# bmsMaster_main.net
KiCad netlist of a schematic drawn in Altium Designer
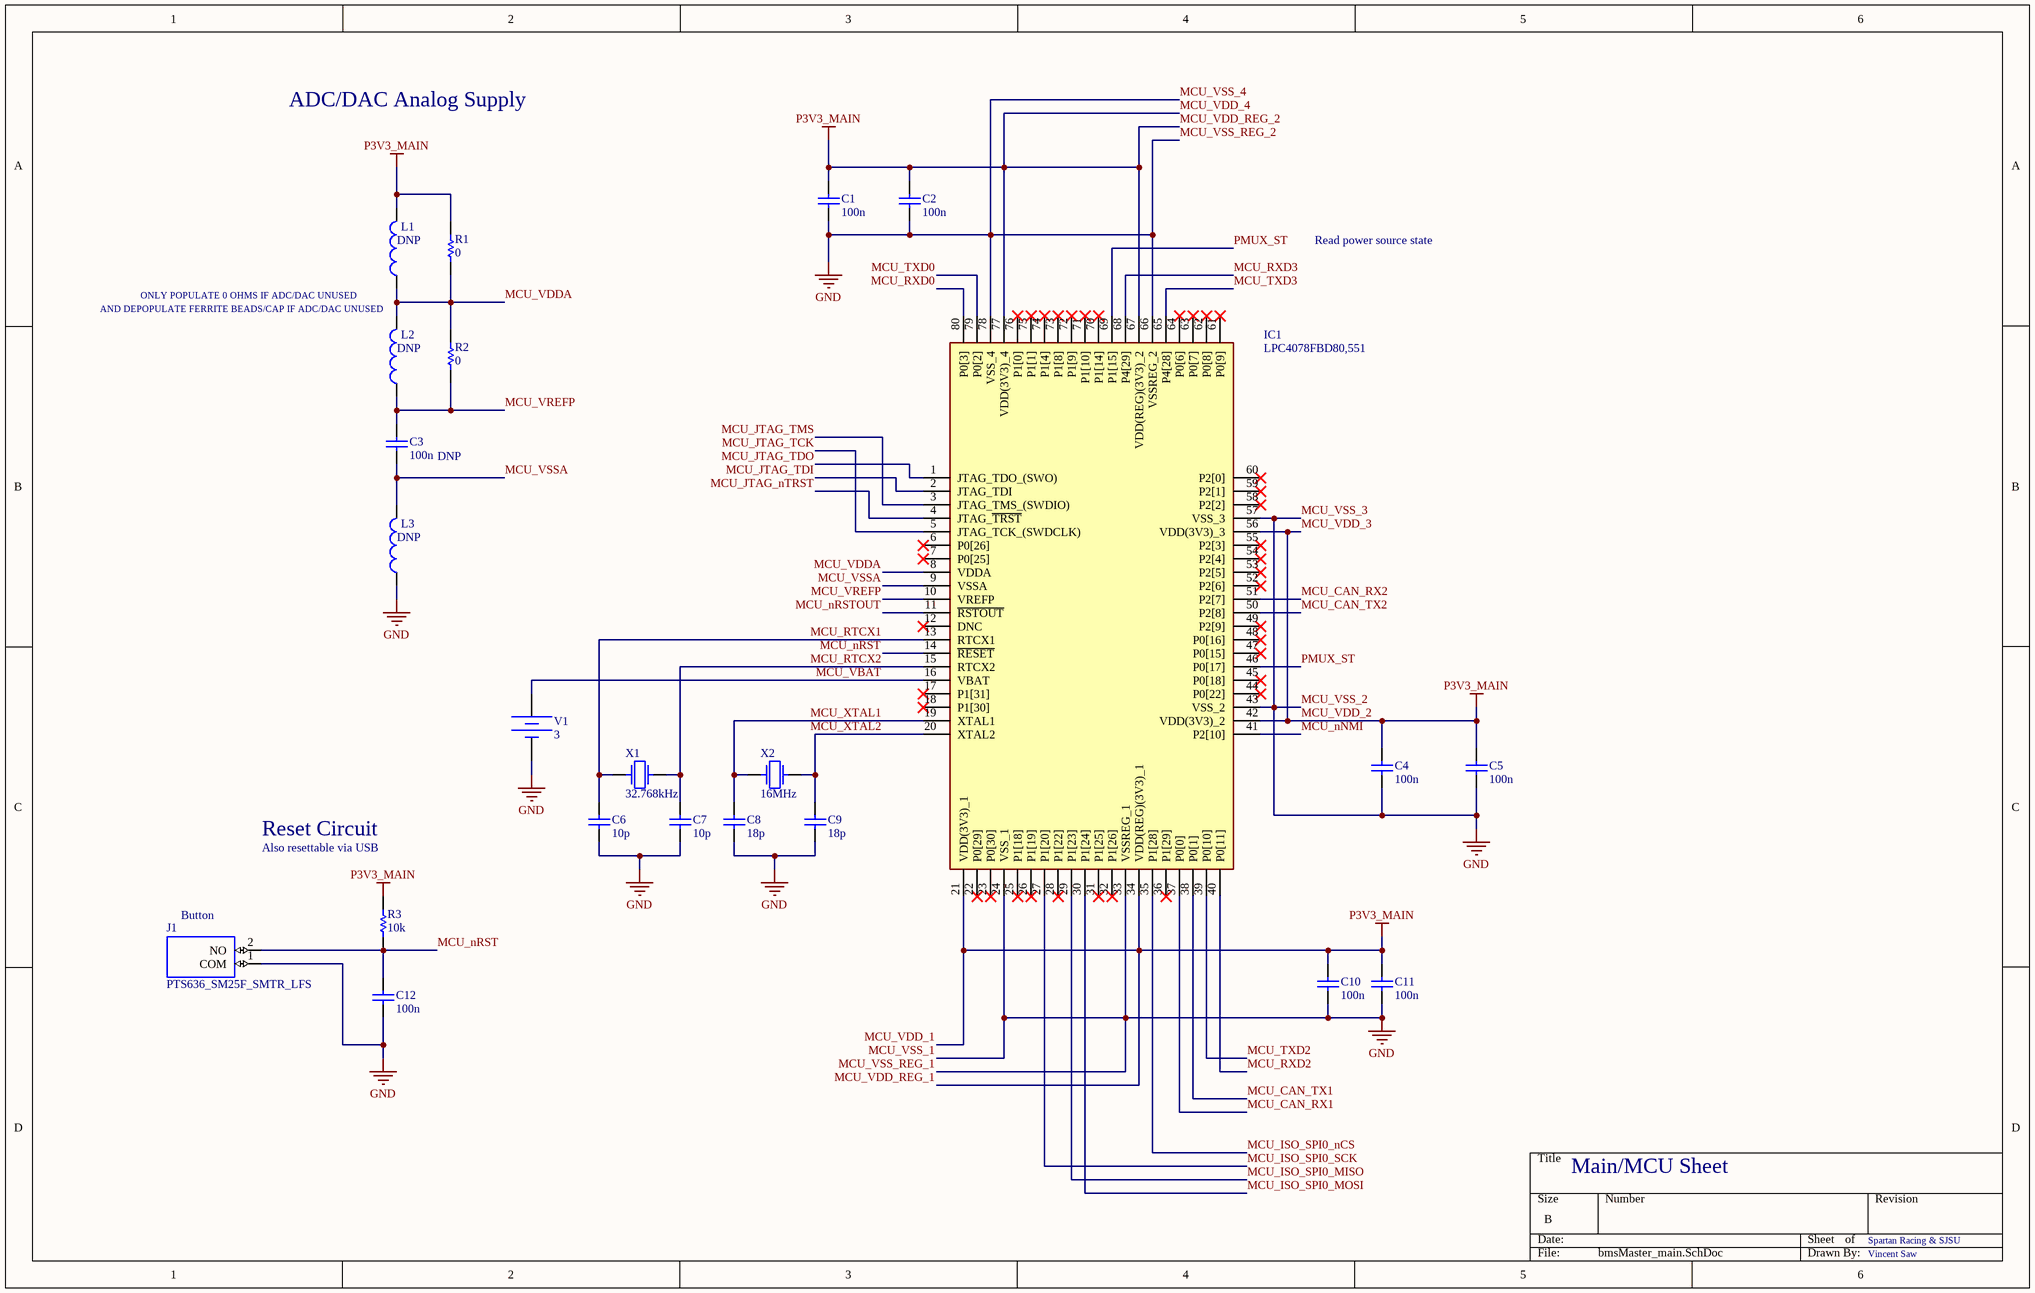
[diagram p0: bmsMaster_main.SchDoc]

(export (version "E")
  (design (tool "Eeschema 10.0.6"))
  (components
    (comp (ref "C1")
      (value "100n")
      (description "Capacitor")
      (libsource (lib "Simulation Generic Components") (part "Capacitor"))
    )
    (comp (ref "C2")
      (value "100n")
      (description "Capacitor")
      (libsource (lib "Simulation Generic Components") (part "Capacitor"))
    )
    (comp (ref "C3")
      (value "100n")
      (description "Capacitor")
      (libsource (lib "Simulation Generic Components") (part "Capacitor"))
    )
    (comp (ref "C4")
      (value "100n")
      (description "Capacitor")
      (libsource (lib "Simulation Generic Components") (part "Capacitor"))
    )
    (comp (ref "C5")
      (value "100n")
      (description "Capacitor")
      (libsource (lib "Simulation Generic Components") (part "Capacitor"))
    )
    (comp (ref "C6")
      (value "10p")
      (description "Capacitor")
      (libsource (lib "Simulation Generic Components") (part "Capacitor"))
    )
    (comp (ref "C7")
      (value "10p")
      (description "Capacitor")
      (libsource (lib "Simulation Generic Components") (part "Capacitor"))
    )
    (comp (ref "C8")
      (value "18p")
      (description "Capacitor")
      (libsource (lib "Simulation Generic Components") (part "Capacitor"))
    )
    (comp (ref "C9")
      (value "18p")
      (description "Capacitor")
      (libsource (lib "Simulation Generic Components") (part "Capacitor"))
    )
    (comp (ref "C10")
      (value "100n")
      (description "Capacitor")
      (libsource (lib "Simulation Generic Components") (part "Capacitor"))
    )
    (comp (ref "C11")
      (value "100n")
      (description "Capacitor")
      (libsource (lib "Simulation Generic Components") (part "Capacitor"))
    )
    (comp (ref "C12")
      (value "100n")
      (description "Capacitor")
      (libsource (lib "Simulation Generic Components") (part "Capacitor"))
    )
    (comp (ref "IC1")
      (value "LPC4078FBD80,551")
      (footprint "SamacSys:QFP50P1400X1400X160-80N")
      (description "Integrated Circuit")
      (fields (field (name "MOUSER PART NUMBER") "771-LPC4078FBD80551"))
      (libsource (lib "*") (part "LPC4078FBD80,551"))
    )
    (comp (ref "J1")
      (value "PTS636_SM25F_SMTR_LFS")
      (footprint "PTS636SM25FSMTRLFS")
      (description "Tactile Switch SPST-NO Top Actuated Surface Mount")
      (fields (field (name "MF") "C&K") (field (name "MP") "PTS636 SM25F SMTR LFS"))
      (libsource (lib "PTS636_SM25F_SMTR_LFS") (part "PTS636_SM25F_SMTR_LFS"))
    )
    (comp (ref "L1") (value "Inductor") (libsource (lib "Simulation Generic Components") (part "Inductor")))
    (comp (ref "L2") (value "Inductor") (libsource (lib "Simulation Generic Components") (part "Inductor")))
    (comp (ref "L3") (value "Inductor") (libsource (lib "Simulation Generic Components") (part "Inductor")))
    (comp (ref "R1")
      (value "0")
      (description "Resistor")
      (libsource (lib "Simulation Generic Components") (part "Resistor"))
    )
    (comp (ref "R2")
      (value "0")
      (description "Resistor")
      (libsource (lib "Simulation Generic Components") (part "Resistor"))
    )
    (comp (ref "R3")
      (value "10k")
      (description "Resistor")
      (libsource (lib "Simulation Generic Components") (part "Resistor"))
    )
    (comp (ref "V1")
      (value "Constant Voltage Source")
      (fields (field (name "DC MAGNITUDE") "3"))
      (libsource (lib "Simulation Generic Components") (part "Battery"))
    )
    (comp (ref "X1")
      (value "Crystal")
      (fields (field (name "F0") "32.768kHz"))
      (libsource (lib "Simulation Generic Components") (part "Crystal"))
    )
    (comp (ref "X2")
      (value "Crystal")
      (fields (field (name "F0") "16MHz"))
      (libsource (lib "Simulation Generic Components") (part "Crystal"))
    )
  )
  (nets
    (net (code "1") (name "/MCU_CAN_RX1") (class "Default")
      (node (ref "IC1") (pin "37") (pinfunction "P0[0]_37") (pintype "passive"))
    )
    (net (code "2") (name "/MCU_CAN_RX2") (class "Default")
      (node (ref "IC1") (pin "51") (pinfunction "P2[7]_51") (pintype "passive"))
    )
    (net (code "3") (name "/MCU_CAN_TX1") (class "Default")
      (node (ref "IC1") (pin "38") (pinfunction "P0[1]_38") (pintype "passive"))
    )
    (net (code "4") (name "/MCU_CAN_TX2") (class "Default")
      (node (ref "IC1") (pin "50") (pinfunction "P2[8]_50") (pintype "passive"))
    )
    (net (code "5") (name "/MCU_ISO_SPI0_MISO") (class "Default")
      (node (ref "IC1") (pin "29") (pinfunction "P1[23]_29") (pintype "passive"))
    )
    (net (code "6") (name "/MCU_ISO_SPI0_MOSI") (class "Default")
      (node (ref "IC1") (pin "30") (pinfunction "P1[24]_30") (pintype "passive"))
    )
    (net (code "7") (name "/MCU_ISO_SPI0_SCK") (class "Default")
      (node (ref "IC1") (pin "27") (pinfunction "P1[20]_27") (pintype "passive"))
    )
    (net (code "8") (name "/MCU_ISO_SPI0_nCS") (class "Default")
      (node (ref "IC1") (pin "35") (pinfunction "P1[28]_35") (pintype "passive"))
    )
    (net (code "9") (name "/MCU_JTAG_TCK") (class "Default")
      (node (ref "IC1") (pin "5") (pinfunction "JTAG_TCK_(SWDCLK)_5") (pintype "passive"))
    )
    (net (code "10") (name "/MCU_JTAG_TDI") (class "Default")
      (node (ref "IC1") (pin "2") (pinfunction "JTAG_TDI_2") (pintype "passive"))
    )
    (net (code "11") (name "/MCU_JTAG_TDO") (class "Default")
      (node (ref "IC1") (pin "1") (pinfunction "JTAG_TDO_(SWO)_1") (pintype "passive"))
    )
    (net (code "12") (name "/MCU_JTAG_TMS") (class "Default")
      (node (ref "IC1") (pin "3") (pinfunction "JTAG_TMS_(SWDIO)_3") (pintype "passive"))
    )
    (net (code "13") (name "/MCU_JTAG_nTRST") (class "Default")
      (node (ref "IC1") (pin "4") (pinfunction "JTAG_~{TRST}_4") (pintype "passive"))
    )
    (net (code "14") (name "/MCU_RTCX1") (class "Default")
      (node (ref "C6") (pin "2") (pinfunction "2_2") (pintype "passive"))
      (node (ref "IC1") (pin "13") (pinfunction "RTCX1_13") (pintype "passive"))
      (node (ref "X1") (pin "1") (pinfunction "1_1") (pintype "passive"))
    )
    (net (code "15") (name "/MCU_RTCX2") (class "Default")
      (node (ref "C7") (pin "2") (pinfunction "2_2") (pintype "passive"))
      (node (ref "IC1") (pin "15") (pinfunction "RTCX2_15") (pintype "passive"))
      (node (ref "X1") (pin "2") (pinfunction "2_2") (pintype "passive"))
    )
    (net (code "16") (name "/MCU_RXD0") (class "Default")
      (node (ref "IC1") (pin "80") (pinfunction "P0[3]_80") (pintype "passive"))
    )
    (net (code "17") (name "/MCU_RXD2") (class "Default")
      (node (ref "IC1") (pin "40") (pinfunction "P0[11]_40") (pintype "passive"))
    )
    (net (code "18") (name "/MCU_RXD3") (class "Default")
      (node (ref "IC1") (pin "68") (pinfunction "P4[29]_68") (pintype "passive"))
    )
    (net (code "19") (name "/MCU_TXD0") (class "Default")
      (node (ref "IC1") (pin "79") (pinfunction "P0[2]_79") (pintype "passive"))
    )
    (net (code "20") (name "/MCU_TXD2") (class "Default")
      (node (ref "IC1") (pin "39") (pinfunction "P0[10]_39") (pintype "passive"))
    )
    (net (code "21") (name "/MCU_TXD3") (class "Default")
      (node (ref "IC1") (pin "65") (pinfunction "P4[28]_65") (pintype "passive"))
    )
    (net (code "22") (name "/MCU_VBAT") (class "Default")
      (node (ref "IC1") (pin "16") (pinfunction "VBAT_16") (pintype "passive"))
      (node (ref "V1") (pin "1") (pinfunction "1_1") (pintype "passive"))
    )
    (net (code "23") (name "/MCU_VDDA") (class "Default")
      (node (ref "IC1") (pin "8") (pinfunction "VDDA_8") (pintype "passive"))
      (node (ref "L1") (pin "1") (pinfunction "1_1") (pintype "passive"))
      (node (ref "L2") (pin "2") (pinfunction "2_2") (pintype "passive"))
      (node (ref "R1") (pin "1") (pinfunction "1_1") (pintype "passive"))
      (node (ref "R2") (pin "2") (pinfunction "2_2") (pintype "passive"))
    )
    (net (code "24") (name "/MCU_VREFP") (class "Default")
      (node (ref "C3") (pin "2") (pinfunction "2_2") (pintype "passive"))
      (node (ref "IC1") (pin "10") (pinfunction "VREFP_10") (pintype "passive"))
      (node (ref "L2") (pin "1") (pinfunction "1_1") (pintype "passive"))
      (node (ref "R2") (pin "1") (pinfunction "1_1") (pintype "passive"))
    )
    (net (code "25") (name "/MCU_VSSA") (class "Default")
      (node (ref "C3") (pin "1") (pinfunction "1_1") (pintype "passive"))
      (node (ref "IC1") (pin "9") (pinfunction "VSSA_9") (pintype "passive"))
      (node (ref "L3") (pin "2") (pinfunction "2_2") (pintype "passive"))
    )
    (net (code "26") (name "/MCU_XTAL1") (class "Default")
      (node (ref "C8") (pin "2") (pinfunction "2_2") (pintype "passive"))
      (node (ref "IC1") (pin "19") (pinfunction "XTAL1_19") (pintype "passive"))
      (node (ref "X2") (pin "1") (pinfunction "1_1") (pintype "passive"))
    )
    (net (code "27") (name "/MCU_XTAL2") (class "Default")
      (node (ref "C9") (pin "2") (pinfunction "2_2") (pintype "passive"))
      (node (ref "IC1") (pin "20") (pinfunction "XTAL2_20") (pintype "passive"))
      (node (ref "X2") (pin "2") (pinfunction "2_2") (pintype "passive"))
    )
    (net (code "28") (name "/MCU_nNMI") (class "Default")
      (node (ref "IC1") (pin "41") (pinfunction "P2[10]_41") (pintype "passive"))
    )
    (net (code "29") (name "/MCU_nRST") (class "Default")
      (node (ref "C12") (pin "2") (pinfunction "2_2") (pintype "passive"))
      (node (ref "IC1") (pin "14") (pinfunction "~{RESET}_14") (pintype "passive"))
      (node (ref "J1") (pin "2") (pinfunction "NO_2") (pintype "bidirectional"))
      (node (ref "R3") (pin "1") (pinfunction "1_1") (pintype "passive"))
    )
    (net (code "30") (name "/MCU_nRSTOUT") (class "Default")
      (node (ref "IC1") (pin "11") (pinfunction "~{RSTOUT}_11") (pintype "passive"))
    )
    (net (code "31") (name "/PMUX_ST") (class "Default")
      (node (ref "IC1") (pin "46") (pinfunction "P0[17]_46") (pintype "passive"))
      (node (ref "IC1") (pin "69") (pinfunction "P1[15]_69") (pintype "passive"))
    )
    (net (code "32") (name "GND") (class "Default")
      (node (ref "C1") (pin "1") (pinfunction "1_1") (pintype "passive"))
      (node (ref "C10") (pin "1") (pinfunction "1_1") (pintype "passive"))
      (node (ref "C11") (pin "1") (pinfunction "1_1") (pintype "passive"))
      (node (ref "C12") (pin "1") (pinfunction "1_1") (pintype "passive"))
      (node (ref "C2") (pin "1") (pinfunction "1_1") (pintype "passive"))
      (node (ref "C4") (pin "1") (pinfunction "1_1") (pintype "passive"))
      (node (ref "C5") (pin "1") (pinfunction "1_1") (pintype "passive"))
      (node (ref "C6") (pin "1") (pinfunction "1_1") (pintype "passive"))
      (node (ref "C7") (pin "1") (pinfunction "1_1") (pintype "passive"))
      (node (ref "C8") (pin "1") (pinfunction "1_1") (pintype "passive"))
      (node (ref "C9") (pin "1") (pinfunction "1_1") (pintype "passive"))
      (node (ref "IC1") (pin "24") (pinfunction "VSS_1_24") (pintype "passive"))
      (node (ref "IC1") (pin "33") (pinfunction "VSSREG_1_33") (pintype "passive"))
      (node (ref "IC1") (pin "43") (pinfunction "VSS_2_43") (pintype "passive"))
      (node (ref "IC1") (pin "57") (pinfunction "VSS_3_57") (pintype "passive"))
      (node (ref "IC1") (pin "66") (pinfunction "VSSREG_2_66") (pintype "passive"))
      (node (ref "IC1") (pin "78") (pinfunction "VSS_4_78") (pintype "passive"))
      (node (ref "J1") (pin "1") (pinfunction "COM_1") (pintype "bidirectional"))
      (node (ref "L3") (pin "1") (pinfunction "1_1") (pintype "passive"))
      (node (ref "V1") (pin "2") (pinfunction "2_2") (pintype "passive"))
    )
    (net (code "33") (name "P3V3_MAIN") (class "Default")
      (node (ref "C1") (pin "2") (pinfunction "2_2") (pintype "passive"))
      (node (ref "C10") (pin "2") (pinfunction "2_2") (pintype "passive"))
      (node (ref "C11") (pin "2") (pinfunction "2_2") (pintype "passive"))
      (node (ref "C2") (pin "2") (pinfunction "2_2") (pintype "passive"))
      (node (ref "C4") (pin "2") (pinfunction "2_2") (pintype "passive"))
      (node (ref "C5") (pin "2") (pinfunction "2_2") (pintype "passive"))
      (node (ref "IC1") (pin "21") (pinfunction "VDD(3V3)_1_21") (pintype "passive"))
      (node (ref "IC1") (pin "34") (pinfunction "VDD(REG)(3V3)_1_34") (pintype "passive"))
      (node (ref "IC1") (pin "42") (pinfunction "VDD(3V3)_2_42") (pintype "passive"))
      (node (ref "IC1") (pin "56") (pinfunction "VDD(3V3)_3_56") (pintype "passive"))
      (node (ref "IC1") (pin "67") (pinfunction "VDD(REG)(3V3)_2_67") (pintype "passive"))
      (node (ref "IC1") (pin "77") (pinfunction "VDD(3V3)_4_77") (pintype "passive"))
      (node (ref "L1") (pin "2") (pinfunction "2_2") (pintype "passive"))
      (node (ref "R1") (pin "2") (pinfunction "2_2") (pintype "passive"))
      (node (ref "R3") (pin "2") (pinfunction "2_2") (pintype "passive"))
    )
    (net (code "34") (name "unconnected-(IC1-DNC-Pad12)") (class "Default")
      (node (ref "IC1") (pin "12") (pinfunction "DNC_12") (pintype "passive+no_connect"))
    )
    (net (code "35") (name "unconnected-(IC1-P0[6]-Pad64)") (class "Default")
      (node (ref "IC1") (pin "64") (pinfunction "P0[6]_64") (pintype "passive+no_connect"))
    )
    (net (code "36") (name "unconnected-(IC1-P0[7]-Pad63)") (class "Default")
      (node (ref "IC1") (pin "63") (pinfunction "P0[7]_63") (pintype "passive+no_connect"))
    )
    (net (code "37") (name "unconnected-(IC1-P0[8]-Pad62)") (class "Default")
      (node (ref "IC1") (pin "62") (pinfunction "P0[8]_62") (pintype "passive+no_connect"))
    )
    (net (code "38") (name "unconnected-(IC1-P0[9]-Pad61)") (class "Default")
      (node (ref "IC1") (pin "61") (pinfunction "P0[9]_61") (pintype "passive+no_connect"))
    )
    (net (code "39") (name "unconnected-(IC1-P0[15]-Pad47)") (class "Default")
      (node (ref "IC1") (pin "47") (pinfunction "P0[15]_47") (pintype "passive+no_connect"))
    )
    (net (code "40") (name "unconnected-(IC1-P0[16]-Pad48)") (class "Default")
      (node (ref "IC1") (pin "48") (pinfunction "P0[16]_48") (pintype "passive+no_connect"))
    )
    (net (code "41") (name "unconnected-(IC1-P0[18]-Pad45)") (class "Default")
      (node (ref "IC1") (pin "45") (pinfunction "P0[18]_45") (pintype "passive+no_connect"))
    )
    (net (code "42") (name "unconnected-(IC1-P0[22]-Pad44)") (class "Default")
      (node (ref "IC1") (pin "44") (pinfunction "P0[22]_44") (pintype "passive+no_connect"))
    )
    (net (code "43") (name "unconnected-(IC1-P0[25]-Pad7)") (class "Default")
      (node (ref "IC1") (pin "7") (pinfunction "P0[25]_7") (pintype "passive+no_connect"))
    )
    (net (code "44") (name "unconnected-(IC1-P0[26]-Pad6)") (class "Default")
      (node (ref "IC1") (pin "6") (pinfunction "P0[26]_6") (pintype "passive+no_connect"))
    )
    (net (code "45") (name "unconnected-(IC1-P0[29]-Pad22)") (class "Default")
      (node (ref "IC1") (pin "22") (pinfunction "P0[29]_22") (pintype "passive+no_connect"))
    )
    (net (code "46") (name "unconnected-(IC1-P0[30]-Pad23)") (class "Default")
      (node (ref "IC1") (pin "23") (pinfunction "P0[30]_23") (pintype "passive+no_connect"))
    )
    (net (code "47") (name "unconnected-(IC1-P1[0]-Pad76)") (class "Default")
      (node (ref "IC1") (pin "76") (pinfunction "P1[0]_76") (pintype "passive+no_connect"))
    )
    (net (code "48") (name "unconnected-(IC1-P1[1]-Pad75)") (class "Default")
      (node (ref "IC1") (pin "75") (pinfunction "P1[1]_75") (pintype "passive+no_connect"))
    )
    (net (code "49") (name "unconnected-(IC1-P1[4]-Pad74)") (class "Default")
      (node (ref "IC1") (pin "74") (pinfunction "P1[4]_74") (pintype "passive+no_connect"))
    )
    (net (code "50") (name "unconnected-(IC1-P1[8]-Pad73)") (class "Default")
      (node (ref "IC1") (pin "73") (pinfunction "P1[8]_73") (pintype "passive+no_connect"))
    )
    (net (code "51") (name "unconnected-(IC1-P1[9]-Pad72)") (class "Default")
      (node (ref "IC1") (pin "72") (pinfunction "P1[9]_72") (pintype "passive+no_connect"))
    )
    (net (code "52") (name "unconnected-(IC1-P1[10]-Pad71)") (class "Default")
      (node (ref "IC1") (pin "71") (pinfunction "P1[10]_71") (pintype "passive+no_connect"))
    )
    (net (code "53") (name "unconnected-(IC1-P1[14]-Pad70)") (class "Default")
      (node (ref "IC1") (pin "70") (pinfunction "P1[14]_70") (pintype "passive+no_connect"))
    )
    (net (code "54") (name "unconnected-(IC1-P1[18]-Pad25)") (class "Default")
      (node (ref "IC1") (pin "25") (pinfunction "P1[18]_25") (pintype "passive+no_connect"))
    )
    (net (code "55") (name "unconnected-(IC1-P1[19]-Pad26)") (class "Default")
      (node (ref "IC1") (pin "26") (pinfunction "P1[19]_26") (pintype "passive+no_connect"))
    )
    (net (code "56") (name "unconnected-(IC1-P1[22]-Pad28)") (class "Default")
      (node (ref "IC1") (pin "28") (pinfunction "P1[22]_28") (pintype "passive+no_connect"))
    )
    (net (code "57") (name "unconnected-(IC1-P1[25]-Pad31)") (class "Default")
      (node (ref "IC1") (pin "31") (pinfunction "P1[25]_31") (pintype "passive+no_connect"))
    )
    (net (code "58") (name "unconnected-(IC1-P1[26]-Pad32)") (class "Default")
      (node (ref "IC1") (pin "32") (pinfunction "P1[26]_32") (pintype "passive+no_connect"))
    )
    (net (code "59") (name "unconnected-(IC1-P1[29]-Pad36)") (class "Default")
      (node (ref "IC1") (pin "36") (pinfunction "P1[29]_36") (pintype "passive+no_connect"))
    )
    (net (code "60") (name "unconnected-(IC1-P1[30]-Pad18)") (class "Default")
      (node (ref "IC1") (pin "18") (pinfunction "P1[30]_18") (pintype "passive+no_connect"))
    )
    (net (code "61") (name "unconnected-(IC1-P1[31]-Pad17)") (class "Default")
      (node (ref "IC1") (pin "17") (pinfunction "P1[31]_17") (pintype "passive+no_connect"))
    )
    (net (code "62") (name "unconnected-(IC1-P2[0]-Pad60)") (class "Default")
      (node (ref "IC1") (pin "60") (pinfunction "P2[0]_60") (pintype "passive+no_connect"))
    )
    (net (code "63") (name "unconnected-(IC1-P2[1]-Pad59)") (class "Default")
      (node (ref "IC1") (pin "59") (pinfunction "P2[1]_59") (pintype "passive+no_connect"))
    )
    (net (code "64") (name "unconnected-(IC1-P2[2]-Pad58)") (class "Default")
      (node (ref "IC1") (pin "58") (pinfunction "P2[2]_58") (pintype "passive+no_connect"))
    )
    (net (code "65") (name "unconnected-(IC1-P2[3]-Pad55)") (class "Default")
      (node (ref "IC1") (pin "55") (pinfunction "P2[3]_55") (pintype "passive+no_connect"))
    )
    (net (code "66") (name "unconnected-(IC1-P2[4]-Pad54)") (class "Default")
      (node (ref "IC1") (pin "54") (pinfunction "P2[4]_54") (pintype "passive+no_connect"))
    )
    (net (code "67") (name "unconnected-(IC1-P2[5]-Pad53)") (class "Default")
      (node (ref "IC1") (pin "53") (pinfunction "P2[5]_53") (pintype "passive+no_connect"))
    )
    (net (code "68") (name "unconnected-(IC1-P2[6]-Pad52)") (class "Default")
      (node (ref "IC1") (pin "52") (pinfunction "P2[6]_52") (pintype "passive+no_connect"))
    )
    (net (code "69") (name "unconnected-(IC1-P2[9]-Pad49)") (class "Default")
      (node (ref "IC1") (pin "49") (pinfunction "P2[9]_49") (pintype "passive+no_connect"))
    )
  )
)
